# 2_mcu.net
KiCad netlist of a schematic drawn in Altium Designer
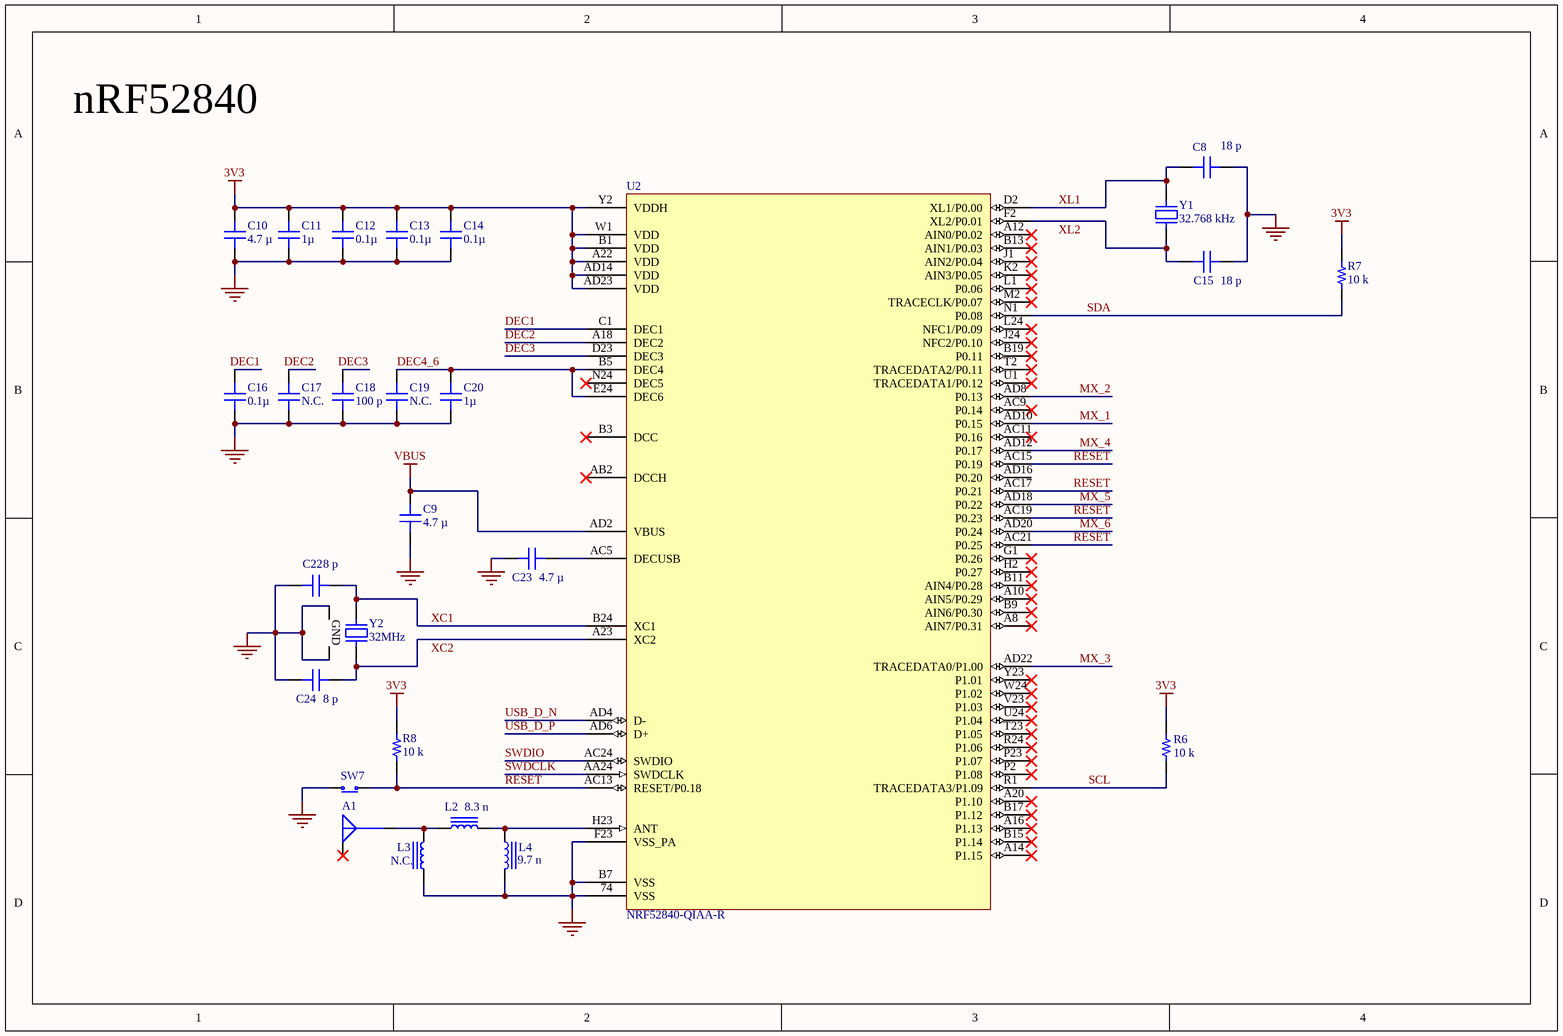
[diagram p0: 2_mcu.SchDoc]

(export (version "E")
  (design (tool "Eeschema 10.0.6"))
  (components
    (comp (ref "A1")
      (value "AMCA31-2R450G-S1F-T3")
      (footprint "FP-AMCA31-MFG")
      (libsource (lib "University of South Florida") (part "AMCA31-2R450G-S1F"))
    )
    (comp (ref "C8")
      (value "18 p")
      (footprint "CAP 0402_1005")
      (description "CAP CER 18PF 100V C0G/NP0 0402")
      (fields (field (name "PART NUMBER") "HMK105CG180JV-F") (field (name "MANUFACTURER") "Taiyo Yuden"))
      (libsource (lib "Celestial Altium Library - altium_library") (part "Capacitor"))
    )
    (comp (ref "C9")
      (value "4.7 µ")
      (footprint "CAP 0402_1005")
      (description "CAP CER 4.7UF 16V X5R 0402")
      (fields
        (field (name "PART NUMBER") "CL05A475MO5NUNC")
        (field (name "MANUFACTURER") "Samsung Electro-Mechanics")
      )
      (libsource (lib "Celestial Altium Library - altium_library") (part "Capacitor"))
    )
    (comp (ref "C10")
      (value "4.7 µ")
      (footprint "CAP 0402_1005")
      (description "CAP CER 4.7UF 16V X5R 0402")
      (fields
        (field (name "PART NUMBER") "CL05A475MO5NUNC")
        (field (name "MANUFACTURER") "Samsung Electro-Mechanics")
      )
      (libsource (lib "Celestial Altium Library - altium_library") (part "Capacitor"))
    )
    (comp (ref "C11")
      (value "1µ")
      (footprint "CAP 0402_1005")
      (description "CAP CER 1UF 10V X5R 0402")
      (fields (field (name "PART NUMBER") "885012105012") (field (name "MANUFACTURER") "Würth Elektronik"))
      (libsource (lib "Celestial Altium Library - altium_library") (part "Capacitor"))
    )
    (comp (ref "C12")
      (value "0.1µ")
      (footprint "CAP 0402_1005")
      (description "CAP CER 0.1UF 10V X7R 0402")
      (fields (field (name "PART NUMBER") "0402ZC104KAT2A") (field (name "MANUFACTURER") "AVX Corporation"))
      (libsource (lib "Celestial Altium Library - altium_library") (part "Capacitor"))
    )
    (comp (ref "C13")
      (value "0.1µ")
      (footprint "CAP 0402_1005")
      (description "CAP CER 0.1UF 10V X7R 0402")
      (fields (field (name "PART NUMBER") "0402ZC104KAT2A") (field (name "MANUFACTURER") "AVX Corporation"))
      (libsource (lib "Celestial Altium Library - altium_library") (part "Capacitor"))
    )
    (comp (ref "C14")
      (value "0.1µ")
      (footprint "CAP 0402_1005")
      (description "CAP CER 0.1UF 10V X7R 0402")
      (fields (field (name "PART NUMBER") "0402ZC104KAT2A") (field (name "MANUFACTURER") "AVX Corporation"))
      (libsource (lib "Celestial Altium Library - altium_library") (part "Capacitor"))
    )
    (comp (ref "C15")
      (value "18 p")
      (footprint "CAP 0402_1005")
      (description "CAP CER 18PF 100V C0G/NP0 0402")
      (fields (field (name "PART NUMBER") "HMK105CG180JV-F") (field (name "MANUFACTURER") "Taiyo Yuden"))
      (libsource (lib "Celestial Altium Library - altium_library") (part "Capacitor"))
    )
    (comp (ref "C16")
      (value "0.1µ")
      (footprint "CAP 0402_1005")
      (description "CAP CER 0.1UF 10V X7R 0402")
      (fields (field (name "PART NUMBER") "0402ZC104KAT2A") (field (name "MANUFACTURER") "AVX Corporation"))
      (libsource (lib "Celestial Altium Library - altium_library") (part "Capacitor"))
    )
    (comp (ref "C17")
      (value "N.C.")
      (footprint "CAP 0402_1005")
      (description "CAP CER 0.1UF 10V X7R 0402")
      (fields (field (name "PART NUMBER") "0402ZC104KAT2A") (field (name "MANUFACTURER") "AVX Corporation"))
      (libsource (lib "Celestial Altium Library - altium_library") (part "Capacitor"))
    )
    (comp (ref "C18")
      (value "100 p")
      (footprint "CAP 0402_1005")
      (description "CAP CER 100PF 50V C0G/NP0 0402")
      (fields
        (field (name "PART NUMBER") "500X07N101MV4T")
        (field (name "MANUFACTURER") "Johanson Dielectrics Inc.")
      )
      (libsource (lib "Celestial Altium Library - altium_library") (part "Capacitor"))
    )
    (comp (ref "C19")
      (value "N.C.")
      (footprint "CAP 0402_1005")
      (description "CAP CER 0.1UF 10V X7R 0402")
      (fields (field (name "PART NUMBER") "0402ZC104KAT2A") (field (name "MANUFACTURER") "AVX Corporation"))
      (libsource (lib "Celestial Altium Library - altium_library") (part "Capacitor"))
    )
    (comp (ref "C20")
      (value "1µ")
      (footprint "CAP 0402_1005")
      (description "CAP CER 1UF 10V X5R 0402")
      (fields (field (name "PART NUMBER") "885012105012") (field (name "MANUFACTURER") "Würth Elektronik"))
      (libsource (lib "Celestial Altium Library - altium_library") (part "Capacitor"))
    )
    (comp (ref "C22")
      (value "8 p")
      (footprint "CAP 0402_1005")
      (description "CAP CER 8PF 50V NP0 0402")
      (fields
        (field (name "PART NUMBER") "C1005NP01H080D050BA")
        (field (name "MANUFACTURER") "TDK Corporation")
      )
      (libsource (lib "Celestial Altium Library - altium_library") (part "Capacitor"))
    )
    (comp (ref "C23")
      (value "4.7 µ")
      (footprint "CAP 0402_1005")
      (description "CAP CER 4.7UF 16V X5R 0402")
      (fields
        (field (name "PART NUMBER") "CL05A475MO5NUNC")
        (field (name "MANUFACTURER") "Samsung Electro-Mechanics")
      )
      (libsource (lib "Celestial Altium Library - altium_library") (part "Capacitor"))
    )
    (comp (ref "C24")
      (value "8 p")
      (footprint "CAP 0402_1005")
      (description "CAP CER 8PF 50V NP0 0402")
      (fields
        (field (name "PART NUMBER") "C1005NP01H080D050BA")
        (field (name "MANUFACTURER") "TDK Corporation")
      )
      (libsource (lib "Celestial Altium Library - altium_library") (part "Capacitor"))
    )
    (comp (ref "L2")
      (value "8.3 n")
      (footprint "IND 0402_1005")
      (description "FIXED IND 8.3NH 1.5A 0.069OHM SM")
      (fields
        (field (name "PART NUMBER") "LQW15AN8N3G80D")
        (field (name "MANUFACTURER") "Murata Electronics")
      )
      (libsource (lib "Celestial Altium Library - altium_library") (part "Inductor"))
    )
    (comp (ref "L3")
      (value "N.C.")
      (footprint "IND 0402_1005")
      (description "FIXED IND 8.3NH 1.5A 0.069OHM SM")
      (fields
        (field (name "PART NUMBER") "LQW15AN8N3G80D")
        (field (name "MANUFACTURER") "Murata Electronics")
      )
      (libsource (lib "Celestial Altium Library - altium_library") (part "Inductor"))
    )
    (comp (ref "L4")
      (value "9.7 n")
      (footprint "IND 0402_1005")
      (description "FIXED IND 9.7NH 1.4A 81 MOHM SMD")
      (fields
        (field (name "PART NUMBER") "LQW15AN9N7J80D")
        (field (name "MANUFACTURER") "Murata Electronics")
      )
      (libsource (lib "Celestial Altium Library - altium_library") (part "Inductor"))
    )
    (comp (ref "R6")
      (value "10 k")
      (footprint "RES 0402_1005")
      (description "RES 10K OHM 0.1% 1/10W 0402")
      (fields
        (field (name "PART NUMBER") "RP73PF1E10KBTD")
        (field (name "MANUFACTURER") "TE Connectivity Passive Product")
      )
      (libsource (lib "Celestial Altium Library - altium_library") (part "Resistor"))
    )
    (comp (ref "R7")
      (value "10 k")
      (footprint "RES 0402_1005")
      (description "RES 10K OHM 0.1% 1/10W 0402")
      (fields
        (field (name "PART NUMBER") "RP73PF1E10KBTD")
        (field (name "MANUFACTURER") "TE Connectivity Passive Product")
      )
      (libsource (lib "Celestial Altium Library - altium_library") (part "Resistor"))
    )
    (comp (ref "R8")
      (value "10 k")
      (footprint "RES 0402_1005")
      (description "RES 10K OHM 0.1% 1/10W 0402")
      (fields
        (field (name "PART NUMBER") "RP73PF1E10KBTD")
        (field (name "MANUFACTURER") "TE Connectivity Passive Product")
      )
      (libsource (lib "Celestial Altium Library - altium_library") (part "Resistor"))
    )
    (comp (ref "SW7")
      (value "PTS840 GK SMTR LFS")
      (footprint "EVQP7A_J_B_K")
      (description "Microminiature SMT Switch, Side Actuated")
      (fields (field (name "MANUFACTURER") "C&K") (field (name "AUTHOR") "rsk"))
      (libsource (lib "University of South Florida") (part "PTS810 SJK 250 SMTR LFS"))
    )
    (comp (ref "U2")
      (value "NRF52840-QIAA-R")
      (footprint "NRSC-AQFN-73")
      (fields (field (name "JLCPCB PART #") "C190794"))
      (libsource (lib "University of South Florida") (part "NRSC-NRF52840-AQFN-73"))
    )
    (comp (ref "Y1")
      (value "32.768 kHz")
      (footprint "ABRACON ABS06")
      (description "CRYSTAL 32.7680KHZ 12.5PF SMD")
      (fields (field (name "PART NUMBER") "ABS06-32.768KHZ-1-T") (field (name "MANUFACTURER") "Abracon LLC"))
      (libsource (lib "Celestial Altium Library - altium_library") (part "Abracon Crystal ABS06"))
    )
    (comp (ref "Y2")
      (value "32MHz")
      (footprint "BT-XTAL_2016")
      (description "32 MHz ±10ppm Crystal 8pF 60 Ohms 4-SMD, No Lead")
      (fields
        (field (name "MANUFACTURER PART #") "XRCGB32M000F1H01R0")
        (field (name "JLCPCB PART #") "C914155")
      )
      (libsource (lib "University of South Florida") (part "XRCGB32M000F1H01R0"))
    )
  )
  (nets
    (net (code "1") (name "/DEC1") (class "Default")
      (node (ref "C16") (pin "2") (pinfunction "2_2") (pintype "passive"))
      (node (ref "U2") (pin "C1") (pinfunction "DEC1_C1") (pintype "power_in"))
    )
    (net (code "2") (name "/DEC2") (class "Default")
      (node (ref "C17") (pin "2") (pinfunction "2_2") (pintype "passive"))
      (node (ref "U2") (pin "A18") (pinfunction "DEC2_A18") (pintype "power_in"))
    )
    (net (code "3") (name "/DEC3") (class "Default")
      (node (ref "C18") (pin "2") (pinfunction "2_2") (pintype "passive"))
      (node (ref "U2") (pin "D23") (pinfunction "DEC3_D23") (pintype "power_in"))
    )
    (net (code "4") (name "/DEC4_6") (class "Default")
      (node (ref "C19") (pin "2") (pinfunction "2_2") (pintype "passive"))
      (node (ref "C20") (pin "2") (pinfunction "2_2") (pintype "passive"))
      (node (ref "U2") (pin "B5") (pinfunction "DEC4_B5") (pintype "power_in"))
      (node (ref "U2") (pin "E24") (pinfunction "DEC6_E24") (pintype "power_in"))
    )
    (net (code "5") (name "/MX_1") (class "Default")
      (node (ref "U2") (pin "AD10") (pinfunction "P0.15_AD10") (pintype "bidirectional"))
    )
    (net (code "6") (name "/MX_2") (class "Default")
      (node (ref "U2") (pin "AD8") (pinfunction "P0.13_AD8") (pintype "bidirectional"))
    )
    (net (code "7") (name "/MX_3") (class "Default")
      (node (ref "U2") (pin "AD22") (pinfunction "TRACEDATA0/P1.00_AD22") (pintype "bidirectional"))
    )
    (net (code "8") (name "/MX_4") (class "Default")
      (node (ref "U2") (pin "AD12") (pinfunction "P0.17_AD12") (pintype "bidirectional"))
    )
    (net (code "9") (name "/MX_5") (class "Default")
      (node (ref "U2") (pin "AD18") (pinfunction "P0.22_AD18") (pintype "bidirectional"))
    )
    (net (code "10") (name "/MX_6") (class "Default")
      (node (ref "U2") (pin "AD20") (pinfunction "P0.24_AD20") (pintype "bidirectional"))
    )
    (net (code "11") (name "/RESET") (class "Default")
      (node (ref "R8") (pin "2") (pinfunction "2_2") (pintype "passive"))
      (node (ref "SW7") (pin "2") (pinfunction "COM_2") (pintype "passive"))
      (node (ref "U2") (pin "AC13") (pinfunction "RESET/P0.18_AC13") (pintype "bidirectional"))
      (node (ref "U2") (pin "AC15") (pinfunction "P0.19_AC15") (pintype "bidirectional"))
      (node (ref "U2") (pin "AC17") (pinfunction "P0.21_AC17") (pintype "bidirectional"))
      (node (ref "U2") (pin "AC19") (pinfunction "P0.23_AC19") (pintype "bidirectional"))
      (node (ref "U2") (pin "AC21") (pinfunction "P0.25_AC21") (pintype "bidirectional"))
    )
    (net (code "12") (name "/SCL") (class "Default")
      (node (ref "R6") (pin "2") (pinfunction "2_2") (pintype "passive"))
      (node (ref "U2") (pin "R1") (pinfunction "TRACEDATA3/P1.09_R1") (pintype "bidirectional"))
    )
    (net (code "13") (name "/SDA") (class "Default")
      (node (ref "R7") (pin "1") (pinfunction "1_1") (pintype "passive"))
      (node (ref "U2") (pin "N1") (pinfunction "P0.08_N1") (pintype "bidirectional"))
    )
    (net (code "14") (name "/SWDCLK") (class "Default")
      (node (ref "U2") (pin "AA24") (pinfunction "SWDCLK_AA24") (pintype "input"))
    )
    (net (code "15") (name "/SWDIO") (class "Default")
      (node (ref "U2") (pin "AC24") (pinfunction "SWDIO_AC24") (pintype "bidirectional"))
    )
    (net (code "16") (name "/USB_D_N") (class "Default")
      (node (ref "U2") (pin "AD4") (pinfunction "D-_AD4") (pintype "bidirectional"))
    )
    (net (code "17") (name "/USB_D_P") (class "Default")
      (node (ref "U2") (pin "AD6") (pinfunction "D+_AD6") (pintype "bidirectional"))
    )
    (net (code "18") (name "/XC1") (class "Default")
      (node (ref "C22") (pin "2") (pinfunction "2_2") (pintype "passive"))
      (node (ref "U2") (pin "B24") (pinfunction "XC1_B24") (pintype "passive"))
      (node (ref "Y2") (pin "1") (pinfunction "IN_1") (pintype "passive"))
    )
    (net (code "19") (name "/XC2") (class "Default")
      (node (ref "C24") (pin "2") (pinfunction "2_2") (pintype "passive"))
      (node (ref "U2") (pin "A23") (pinfunction "XC2_A23") (pintype "passive"))
      (node (ref "Y2") (pin "3") (pinfunction "OUT_3") (pintype "passive"))
    )
    (net (code "20") (name "/XL1") (class "Default")
      (node (ref "C8") (pin "1") (pinfunction "1_1") (pintype "passive"))
      (node (ref "U2") (pin "D2") (pinfunction "XL1/P0.00_D2") (pintype "bidirectional"))
      (node (ref "Y1") (pin "2") (pinfunction "2_2") (pintype "passive"))
    )
    (net (code "21") (name "/XL2") (class "Default")
      (node (ref "C15") (pin "1") (pinfunction "1_1") (pintype "passive"))
      (node (ref "U2") (pin "F2") (pinfunction "XL2/P0.01_F2") (pintype "bidirectional"))
      (node (ref "Y1") (pin "1") (pinfunction "1_1") (pintype "passive"))
    )
    (net (code "22") (name "3V3") (class "Default")
      (node (ref "C10") (pin "2") (pinfunction "2_2") (pintype "passive"))
      (node (ref "C11") (pin "2") (pinfunction "2_2") (pintype "passive"))
      (node (ref "C12") (pin "2") (pinfunction "2_2") (pintype "passive"))
      (node (ref "C13") (pin "2") (pinfunction "2_2") (pintype "passive"))
      (node (ref "C14") (pin "2") (pinfunction "2_2") (pintype "passive"))
      (node (ref "R6") (pin "1") (pinfunction "1_1") (pintype "passive"))
      (node (ref "R7") (pin "2") (pinfunction "2_2") (pintype "passive"))
      (node (ref "R8") (pin "1") (pinfunction "1_1") (pintype "passive"))
      (node (ref "U2") (pin "A22") (pinfunction "VDD_A22") (pintype "power_in"))
      (node (ref "U2") (pin "AD14") (pinfunction "VDD_AD14") (pintype "power_in"))
      (node (ref "U2") (pin "AD23") (pinfunction "VDD_AD23") (pintype "power_in"))
      (node (ref "U2") (pin "B1") (pinfunction "VDD_B1") (pintype "power_in"))
      (node (ref "U2") (pin "W1") (pinfunction "VDD_W1") (pintype "power_in"))
      (node (ref "U2") (pin "Y2") (pinfunction "VDDH_Y2") (pintype "power_in"))
    )
    (net (code "23") (name "GND") (class "Default")
      (node (ref "C10") (pin "1") (pinfunction "1_1") (pintype "passive"))
      (node (ref "C11") (pin "1") (pinfunction "1_1") (pintype "passive"))
      (node (ref "C12") (pin "1") (pinfunction "1_1") (pintype "passive"))
      (node (ref "C13") (pin "1") (pinfunction "1_1") (pintype "passive"))
      (node (ref "C14") (pin "1") (pinfunction "1_1") (pintype "passive"))
      (node (ref "C15") (pin "2") (pinfunction "2_2") (pintype "passive"))
      (node (ref "C16") (pin "1") (pinfunction "1_1") (pintype "passive"))
      (node (ref "C17") (pin "1") (pinfunction "1_1") (pintype "passive"))
      (node (ref "C18") (pin "1") (pinfunction "1_1") (pintype "passive"))
      (node (ref "C19") (pin "1") (pinfunction "1_1") (pintype "passive"))
      (node (ref "C20") (pin "1") (pinfunction "1_1") (pintype "passive"))
      (node (ref "C22") (pin "1") (pinfunction "1_1") (pintype "passive"))
      (node (ref "C23") (pin "2") (pinfunction "2_2") (pintype "passive"))
      (node (ref "C24") (pin "1") (pinfunction "1_1") (pintype "passive"))
      (node (ref "C8") (pin "2") (pinfunction "2_2") (pintype "passive"))
      (node (ref "C9") (pin "1") (pinfunction "1_1") (pintype "passive"))
      (node (ref "L3") (pin "1") (pinfunction "1_1") (pintype "passive"))
      (node (ref "L4") (pin "2") (pinfunction "2_2") (pintype "passive"))
      (node (ref "SW7") (pin "1") (pinfunction "N.O_1") (pintype "passive"))
      (node (ref "U2") (pin "74") (pinfunction "VSS_74") (pintype "power_in"))
      (node (ref "U2") (pin "B7") (pinfunction "VSS_B7") (pintype "power_in"))
      (node (ref "U2") (pin "F23") (pinfunction "VSS_PA_F23") (pintype "power_in"))
      (node (ref "Y2") (pin "2") (pinfunction "GND_2") (pintype "passive"))
      (node (ref "Y2") (pin "4") (pinfunction "GND_4") (pintype "passive"))
    )
    (net (code "24") (name "Net-(A1-Feed_Point)") (class "Default")
      (node (ref "A1") (pin "1") (pinfunction "Feed_Point_1") (pintype "passive"))
      (node (ref "L2") (pin "1") (pinfunction "1_1") (pintype "passive"))
      (node (ref "L3") (pin "2") (pinfunction "2_2") (pintype "passive"))
    )
    (net (code "25") (name "Net-(U2-ANT)") (class "Default")
      (node (ref "L2") (pin "2") (pinfunction "2_2") (pintype "passive"))
      (node (ref "L4") (pin "1") (pinfunction "1_1") (pintype "passive"))
      (node (ref "U2") (pin "H23") (pinfunction "ANT_H23") (pintype "input"))
    )
    (net (code "26") (name "Net-(U2-DECUSB)") (class "Default")
      (node (ref "C23") (pin "1") (pinfunction "1_1") (pintype "passive"))
      (node (ref "U2") (pin "AC5") (pinfunction "DECUSB_AC5") (pintype "power_in"))
    )
    (net (code "27") (name "VBUS") (class "Default")
      (node (ref "C9") (pin "2") (pinfunction "2_2") (pintype "passive"))
      (node (ref "U2") (pin "AD2") (pinfunction "VBUS_AD2") (pintype "power_in"))
    )
    (net (code "28") (name "unconnected-(A1-NC-Pad2)") (class "Default")
      (node (ref "A1") (pin "2") (pinfunction "NC_2") (pintype "passive+no_connect"))
    )
    (net (code "29") (name "unconnected-(U2-AIN0{slash}P0.02-PadA12)") (class "Default")
      (node (ref "U2") (pin "A12") (pinfunction "AIN0/P0.02_A12") (pintype "bidirectional+no_connect"))
    )
    (net (code "30") (name "unconnected-(U2-AIN1{slash}P0.03-PadB13)") (class "Default")
      (node (ref "U2") (pin "B13") (pinfunction "AIN1/P0.03_B13") (pintype "bidirectional+no_connect"))
    )
    (net (code "31") (name "unconnected-(U2-AIN2{slash}P0.04-PadJ1)") (class "Default")
      (node (ref "U2") (pin "J1") (pinfunction "AIN2/P0.04_J1") (pintype "bidirectional+no_connect"))
    )
    (net (code "32") (name "unconnected-(U2-AIN3{slash}P0.05-PadK2)") (class "Default")
      (node (ref "U2") (pin "K2") (pinfunction "AIN3/P0.05_K2") (pintype "bidirectional+no_connect"))
    )
    (net (code "33") (name "unconnected-(U2-AIN4{slash}P0.28-PadB11)") (class "Default")
      (node (ref "U2") (pin "B11") (pinfunction "AIN4/P0.28_B11") (pintype "bidirectional+no_connect"))
    )
    (net (code "34") (name "unconnected-(U2-AIN5{slash}P0.29-PadA10)") (class "Default")
      (node (ref "U2") (pin "A10") (pinfunction "AIN5/P0.29_A10") (pintype "bidirectional+no_connect"))
    )
    (net (code "35") (name "unconnected-(U2-AIN6{slash}P0.30-PadB9)") (class "Default")
      (node (ref "U2") (pin "B9") (pinfunction "AIN6/P0.30_B9") (pintype "bidirectional+no_connect"))
    )
    (net (code "36") (name "unconnected-(U2-AIN7{slash}P0.31-PadA8)") (class "Default")
      (node (ref "U2") (pin "A8") (pinfunction "AIN7/P0.31_A8") (pintype "bidirectional+no_connect"))
    )
    (net (code "37") (name "unconnected-(U2-DCC-PadB3)") (class "Default")
      (node (ref "U2") (pin "B3") (pinfunction "DCC_B3") (pintype "power_in+no_connect"))
    )
    (net (code "38") (name "unconnected-(U2-DCCH-PadAB2)") (class "Default")
      (node (ref "U2") (pin "AB2") (pinfunction "DCCH_AB2") (pintype "power_in+no_connect"))
    )
    (net (code "39") (name "unconnected-(U2-DEC5-PadN24)") (class "Default")
      (node (ref "U2") (pin "N24") (pinfunction "DEC5_N24") (pintype "power_in+no_connect"))
    )
    (net (code "40") (name "unconnected-(U2-NFC1{slash}P0.09-PadL24)") (class "Default")
      (node (ref "U2") (pin "L24") (pinfunction "NFC1/P0.09_L24") (pintype "bidirectional+no_connect"))
    )
    (net (code "41") (name "unconnected-(U2-NFC2{slash}P0.10-PadJ24)") (class "Default")
      (node (ref "U2") (pin "J24") (pinfunction "NFC2/P0.10_J24") (pintype "bidirectional+no_connect"))
    )
    (net (code "42") (name "unconnected-(U2-P0.06-PadL1)") (class "Default")
      (node (ref "U2") (pin "L1") (pinfunction "P0.06_L1") (pintype "bidirectional+no_connect"))
    )
    (net (code "43") (name "unconnected-(U2-P0.11-PadB19)") (class "Default")
      (node (ref "U2") (pin "B19") (pinfunction "P0.11_B19") (pintype "bidirectional+no_connect"))
    )
    (net (code "44") (name "unconnected-(U2-P0.14-PadAC9)") (class "Default")
      (node (ref "U2") (pin "AC9") (pinfunction "P0.14_AC9") (pintype "bidirectional+no_connect"))
    )
    (net (code "45") (name "unconnected-(U2-P0.16-PadAC11)") (class "Default")
      (node (ref "U2") (pin "AC11") (pinfunction "P0.16_AC11") (pintype "bidirectional+no_connect"))
    )
    (net (code "46") (name "unconnected-(U2-P0.20-PadAD16)") (class "Default")
      (node (ref "U2") (pin "AD16") (pinfunction "P0.20_AD16") (pintype "bidirectional"))
    )
    (net (code "47") (name "unconnected-(U2-P0.26-PadG1)") (class "Default")
      (node (ref "U2") (pin "G1") (pinfunction "P0.26_G1") (pintype "bidirectional+no_connect"))
    )
    (net (code "48") (name "unconnected-(U2-P0.27-PadH2)") (class "Default")
      (node (ref "U2") (pin "H2") (pinfunction "P0.27_H2") (pintype "bidirectional+no_connect"))
    )
    (net (code "49") (name "unconnected-(U2-P1.01-PadY23)") (class "Default")
      (node (ref "U2") (pin "Y23") (pinfunction "P1.01_Y23") (pintype "bidirectional+no_connect"))
    )
    (net (code "50") (name "unconnected-(U2-P1.02-PadW24)") (class "Default")
      (node (ref "U2") (pin "W24") (pinfunction "P1.02_W24") (pintype "bidirectional+no_connect"))
    )
    (net (code "51") (name "unconnected-(U2-P1.03-PadV23)") (class "Default")
      (node (ref "U2") (pin "V23") (pinfunction "P1.03_V23") (pintype "bidirectional+no_connect"))
    )
    (net (code "52") (name "unconnected-(U2-P1.04-PadU24)") (class "Default")
      (node (ref "U2") (pin "U24") (pinfunction "P1.04_U24") (pintype "bidirectional+no_connect"))
    )
    (net (code "53") (name "unconnected-(U2-P1.05-PadT23)") (class "Default")
      (node (ref "U2") (pin "T23") (pinfunction "P1.05_T23") (pintype "bidirectional+no_connect"))
    )
    (net (code "54") (name "unconnected-(U2-P1.06-PadR24)") (class "Default")
      (node (ref "U2") (pin "R24") (pinfunction "P1.06_R24") (pintype "bidirectional+no_connect"))
    )
    (net (code "55") (name "unconnected-(U2-P1.07-PadP23)") (class "Default")
      (node (ref "U2") (pin "P23") (pinfunction "P1.07_P23") (pintype "bidirectional+no_connect"))
    )
    (net (code "56") (name "unconnected-(U2-P1.08-PadP2)") (class "Default")
      (node (ref "U2") (pin "P2") (pinfunction "P1.08_P2") (pintype "bidirectional+no_connect"))
    )
    (net (code "57") (name "unconnected-(U2-P1.10-PadA20)") (class "Default")
      (node (ref "U2") (pin "A20") (pinfunction "P1.10_A20") (pintype "bidirectional+no_connect"))
    )
    (net (code "58") (name "unconnected-(U2-P1.12-PadB17)") (class "Default")
      (node (ref "U2") (pin "B17") (pinfunction "P1.12_B17") (pintype "bidirectional+no_connect"))
    )
    (net (code "59") (name "unconnected-(U2-P1.13-PadA16)") (class "Default")
      (node (ref "U2") (pin "A16") (pinfunction "P1.13_A16") (pintype "bidirectional+no_connect"))
    )
    (net (code "60") (name "unconnected-(U2-P1.14-PadB15)") (class "Default")
      (node (ref "U2") (pin "B15") (pinfunction "P1.14_B15") (pintype "bidirectional+no_connect"))
    )
    (net (code "61") (name "unconnected-(U2-P1.15-PadA14)") (class "Default")
      (node (ref "U2") (pin "A14") (pinfunction "P1.15_A14") (pintype "bidirectional+no_connect"))
    )
    (net (code "62") (name "unconnected-(U2-TRACECLK{slash}P0.07-PadM2)") (class "Default")
      (node (ref "U2") (pin "M2") (pinfunction "TRACECLK/P0.07_M2") (pintype "bidirectional+no_connect"))
    )
    (net (code "63") (name "unconnected-(U2-TRACEDATA1{slash}P0.12-PadU1)") (class "Default")
      (node (ref "U2") (pin "U1") (pinfunction "TRACEDATA1/P0.12_U1") (pintype "bidirectional+no_connect"))
    )
    (net (code "64") (name "unconnected-(U2-TRACEDATA2{slash}P0.11-PadT2)") (class "Default")
      (node (ref "U2") (pin "T2") (pinfunction "TRACEDATA2/P0.11_T2") (pintype "bidirectional+no_connect"))
    )
  )
)
